# UVB_LED_Controller_-_current_balancing.net
KiCad netlist of a schematic drawn in Altium Designer
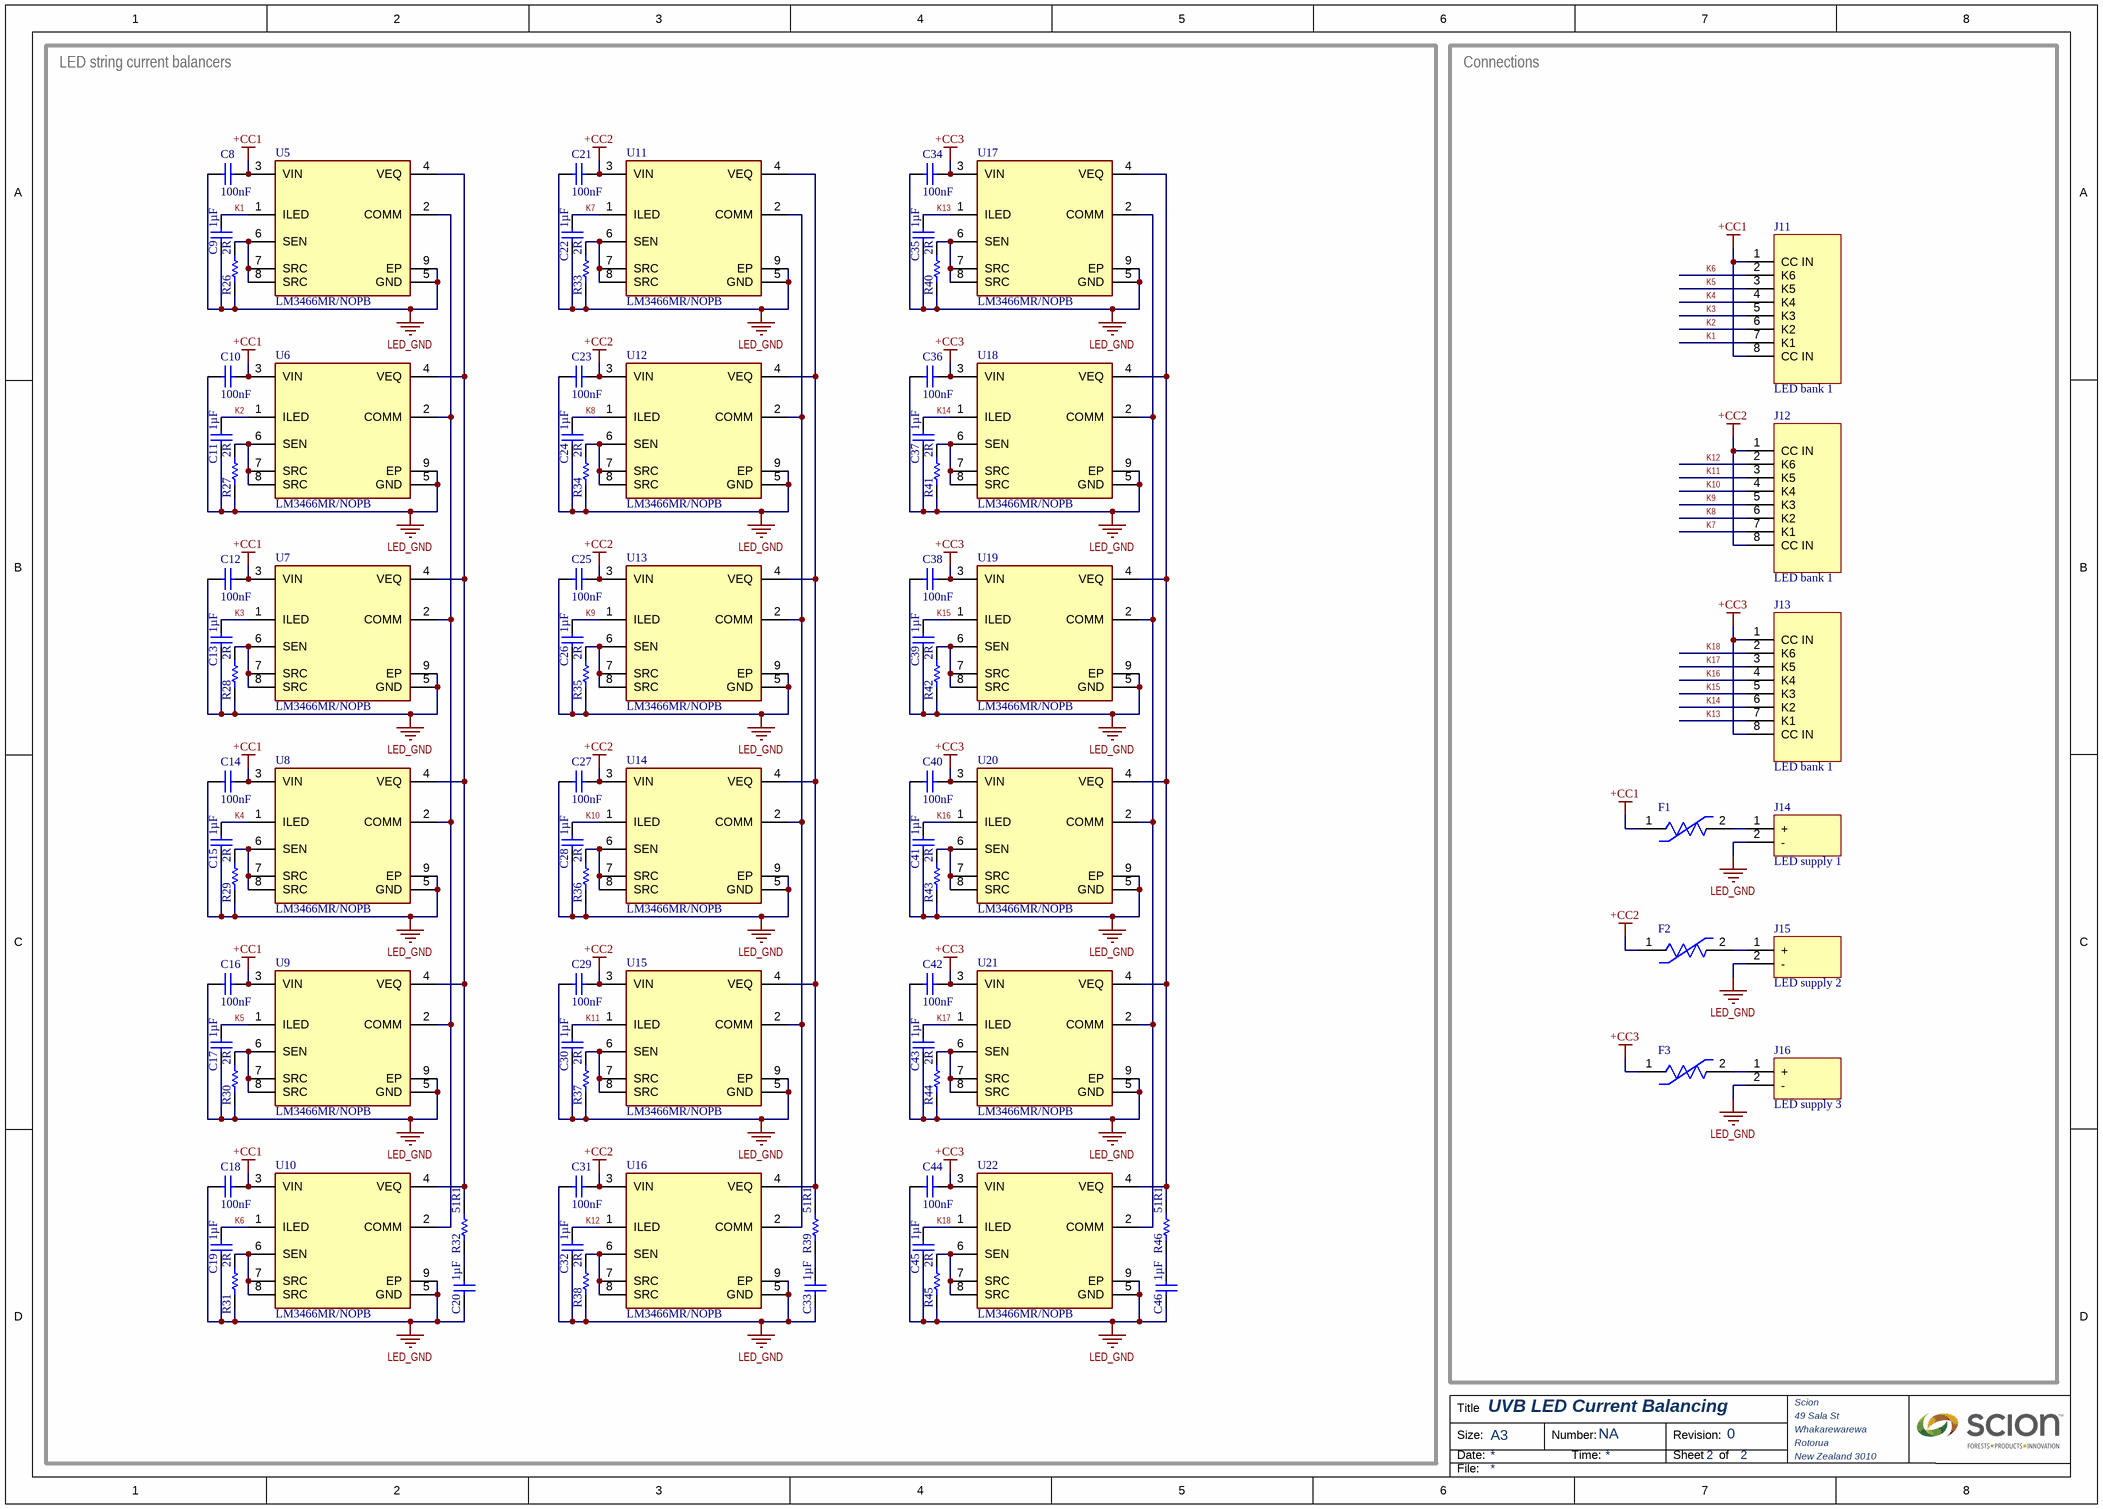
[diagram p0: UVB LED Controller - current balancing.SchDoc]

(export (version "E")
  (design (tool "Eeschema 10.0.6"))
  (components
    (comp (ref "C8")
      (value "100nF")
      (footprint "0603_CAP")
      (description "SMD Capacitor")
      (fields (field (name "Comment") "Capacitor"))
      (libsource (lib "Scion Research") (part "CMP-019-00005-2"))
    )
    (comp (ref "C9")
      (value "1µF")
      (footprint "0603_CAP")
      (description "SMD Capacitor")
      (fields (field (name "Comment") "Capacitor"))
      (libsource (lib "Scion Research") (part "CMP-019-00005-2"))
    )
    (comp (ref "C10")
      (value "100nF")
      (footprint "0603_CAP")
      (description "SMD Capacitor")
      (fields (field (name "Comment") "Capacitor"))
      (libsource (lib "Scion Research") (part "CMP-019-00005-2"))
    )
    (comp (ref "C11")
      (value "1µF")
      (footprint "0603_CAP")
      (description "SMD Capacitor")
      (fields (field (name "Comment") "Capacitor"))
      (libsource (lib "Scion Research") (part "CMP-019-00005-2"))
    )
    (comp (ref "C12")
      (value "100nF")
      (footprint "0603_CAP")
      (description "SMD Capacitor")
      (fields (field (name "Comment") "Capacitor"))
      (libsource (lib "Scion Research") (part "CMP-019-00005-2"))
    )
    (comp (ref "C13")
      (value "1µF")
      (footprint "0603_CAP")
      (description "SMD Capacitor")
      (fields (field (name "Comment") "Capacitor"))
      (libsource (lib "Scion Research") (part "CMP-019-00005-2"))
    )
    (comp (ref "C14")
      (value "100nF")
      (footprint "0603_CAP")
      (description "SMD Capacitor")
      (fields (field (name "Comment") "Capacitor"))
      (libsource (lib "Scion Research") (part "CMP-019-00005-2"))
    )
    (comp (ref "C15")
      (value "1µF")
      (footprint "0603_CAP")
      (description "SMD Capacitor")
      (fields (field (name "Comment") "Capacitor"))
      (libsource (lib "Scion Research") (part "CMP-019-00005-2"))
    )
    (comp (ref "C16")
      (value "100nF")
      (footprint "0603_CAP")
      (description "SMD Capacitor")
      (fields (field (name "Comment") "Capacitor"))
      (libsource (lib "Scion Research") (part "CMP-019-00005-2"))
    )
    (comp (ref "C17")
      (value "1µF")
      (footprint "0603_CAP")
      (description "SMD Capacitor")
      (fields (field (name "Comment") "Capacitor"))
      (libsource (lib "Scion Research") (part "CMP-019-00005-2"))
    )
    (comp (ref "C18")
      (value "100nF")
      (footprint "0603_CAP")
      (description "SMD Capacitor")
      (fields (field (name "Comment") "Capacitor"))
      (libsource (lib "Scion Research") (part "CMP-019-00005-2"))
    )
    (comp (ref "C19")
      (value "1µF")
      (footprint "0603_CAP")
      (description "SMD Capacitor")
      (fields (field (name "Comment") "Capacitor"))
      (libsource (lib "Scion Research") (part "CMP-019-00005-2"))
    )
    (comp (ref "C20")
      (value "1µF")
      (footprint "0603_CAP")
      (description "SMD Capacitor")
      (fields (field (name "Comment") "Capacitor"))
      (libsource (lib "Scion Research") (part "CMP-019-00005-2"))
    )
    (comp (ref "C21")
      (value "100nF")
      (footprint "0603_CAP")
      (description "SMD Capacitor")
      (fields (field (name "Comment") "Capacitor"))
      (libsource (lib "Scion Research") (part "CMP-019-00005-2"))
    )
    (comp (ref "C22")
      (value "1µF")
      (footprint "0603_CAP")
      (description "SMD Capacitor")
      (fields (field (name "Comment") "Capacitor"))
      (libsource (lib "Scion Research") (part "CMP-019-00005-2"))
    )
    (comp (ref "C23")
      (value "100nF")
      (footprint "0603_CAP")
      (description "SMD Capacitor")
      (fields (field (name "Comment") "Capacitor"))
      (libsource (lib "Scion Research") (part "CMP-019-00005-2"))
    )
    (comp (ref "C24")
      (value "1µF")
      (footprint "0603_CAP")
      (description "SMD Capacitor")
      (fields (field (name "Comment") "Capacitor"))
      (libsource (lib "Scion Research") (part "CMP-019-00005-2"))
    )
    (comp (ref "C25")
      (value "100nF")
      (footprint "0603_CAP")
      (description "SMD Capacitor")
      (fields (field (name "Comment") "Capacitor"))
      (libsource (lib "Scion Research") (part "CMP-019-00005-2"))
    )
    (comp (ref "C26")
      (value "1µF")
      (footprint "0603_CAP")
      (description "SMD Capacitor")
      (fields (field (name "Comment") "Capacitor"))
      (libsource (lib "Scion Research") (part "CMP-019-00005-2"))
    )
    (comp (ref "C27")
      (value "100nF")
      (footprint "0603_CAP")
      (description "SMD Capacitor")
      (fields (field (name "Comment") "Capacitor"))
      (libsource (lib "Scion Research") (part "CMP-019-00005-2"))
    )
    (comp (ref "C28")
      (value "1µF")
      (footprint "0603_CAP")
      (description "SMD Capacitor")
      (fields (field (name "Comment") "Capacitor"))
      (libsource (lib "Scion Research") (part "CMP-019-00005-2"))
    )
    (comp (ref "C29")
      (value "100nF")
      (footprint "0603_CAP")
      (description "SMD Capacitor")
      (fields (field (name "Comment") "Capacitor"))
      (libsource (lib "Scion Research") (part "CMP-019-00005-2"))
    )
    (comp (ref "C30")
      (value "1µF")
      (footprint "0603_CAP")
      (description "SMD Capacitor")
      (fields (field (name "Comment") "Capacitor"))
      (libsource (lib "Scion Research") (part "CMP-019-00005-2"))
    )
    (comp (ref "C31")
      (value "100nF")
      (footprint "0603_CAP")
      (description "SMD Capacitor")
      (fields (field (name "Comment") "Capacitor"))
      (libsource (lib "Scion Research") (part "CMP-019-00005-2"))
    )
    (comp (ref "C32")
      (value "1µF")
      (footprint "0603_CAP")
      (description "SMD Capacitor")
      (fields (field (name "Comment") "Capacitor"))
      (libsource (lib "Scion Research") (part "CMP-019-00005-2"))
    )
    (comp (ref "C33")
      (value "1µF")
      (footprint "0603_CAP")
      (description "SMD Capacitor")
      (fields (field (name "Comment") "Capacitor"))
      (libsource (lib "Scion Research") (part "CMP-019-00005-2"))
    )
    (comp (ref "C34")
      (value "100nF")
      (footprint "0603_CAP")
      (description "SMD Capacitor")
      (fields (field (name "Comment") "Capacitor"))
      (libsource (lib "Scion Research") (part "CMP-019-00005-2"))
    )
    (comp (ref "C35")
      (value "1µF")
      (footprint "0603_CAP")
      (description "SMD Capacitor")
      (fields (field (name "Comment") "Capacitor"))
      (libsource (lib "Scion Research") (part "CMP-019-00005-2"))
    )
    (comp (ref "C36")
      (value "100nF")
      (footprint "0603_CAP")
      (description "SMD Capacitor")
      (fields (field (name "Comment") "Capacitor"))
      (libsource (lib "Scion Research") (part "CMP-019-00005-2"))
    )
    (comp (ref "C37")
      (value "1µF")
      (footprint "0603_CAP")
      (description "SMD Capacitor")
      (fields (field (name "Comment") "Capacitor"))
      (libsource (lib "Scion Research") (part "CMP-019-00005-2"))
    )
    (comp (ref "C38")
      (value "100nF")
      (footprint "0603_CAP")
      (description "SMD Capacitor")
      (fields (field (name "Comment") "Capacitor"))
      (libsource (lib "Scion Research") (part "CMP-019-00005-2"))
    )
    (comp (ref "C39")
      (value "1µF")
      (footprint "0603_CAP")
      (description "SMD Capacitor")
      (fields (field (name "Comment") "Capacitor"))
      (libsource (lib "Scion Research") (part "CMP-019-00005-2"))
    )
    (comp (ref "C40")
      (value "100nF")
      (footprint "0603_CAP")
      (description "SMD Capacitor")
      (fields (field (name "Comment") "Capacitor"))
      (libsource (lib "Scion Research") (part "CMP-019-00005-2"))
    )
    (comp (ref "C41")
      (value "1µF")
      (footprint "0603_CAP")
      (description "SMD Capacitor")
      (fields (field (name "Comment") "Capacitor"))
      (libsource (lib "Scion Research") (part "CMP-019-00005-2"))
    )
    (comp (ref "C42")
      (value "100nF")
      (footprint "0603_CAP")
      (description "SMD Capacitor")
      (fields (field (name "Comment") "Capacitor"))
      (libsource (lib "Scion Research") (part "CMP-019-00005-2"))
    )
    (comp (ref "C43")
      (value "1µF")
      (footprint "0603_CAP")
      (description "SMD Capacitor")
      (fields (field (name "Comment") "Capacitor"))
      (libsource (lib "Scion Research") (part "CMP-019-00005-2"))
    )
    (comp (ref "C44")
      (value "100nF")
      (footprint "0603_CAP")
      (description "SMD Capacitor")
      (fields (field (name "Comment") "Capacitor"))
      (libsource (lib "Scion Research") (part "CMP-019-00005-2"))
    )
    (comp (ref "C45")
      (value "1µF")
      (footprint "0603_CAP")
      (description "SMD Capacitor")
      (fields (field (name "Comment") "Capacitor"))
      (libsource (lib "Scion Research") (part "CMP-019-00005-2"))
    )
    (comp (ref "C46")
      (value "1µF")
      (footprint "0603_CAP")
      (description "SMD Capacitor")
      (fields (field (name "Comment") "Capacitor"))
      (libsource (lib "Scion Research") (part "CMP-019-00005-2"))
    )
    (comp (ref "F1")
      (value "0ZCF0100AF2A")
      (footprint "FP-0ZCF0100AF2A-MFG")
      (description "PTC Resettable Fuse 100A 0.5s 60VDC 0.09 Ohm 2-Pin 2920 T/R")
      (libsource (lib "Scion Research") (part "CMP-00051-1"))
    )
    (comp (ref "F2")
      (value "0ZCF0100AF2A")
      (footprint "FP-0ZCF0100AF2A-MFG")
      (description "PTC Resettable Fuse 100A 0.5s 60VDC 0.09 Ohm 2-Pin 2920 T/R")
      (libsource (lib "Scion Research") (part "CMP-00051-1"))
    )
    (comp (ref "F3")
      (value "0ZCF0100AF2A")
      (footprint "FP-0ZCF0100AF2A-MFG")
      (description "PTC Resettable Fuse 100A 0.5s 60VDC 0.09 Ohm 2-Pin 2920 T/R")
      (libsource (lib "Scion Research") (part "CMP-00051-1"))
    )
    (comp (ref "J11")
      (value "LED bank 1")
      (footprint "8P RA MOLEX Clik-MATE 1.5mm")
      (description "8 Pin Connector")
      (libsource (lib "Scion Research") (part "CMP-002-00084-5"))
    )
    (comp (ref "J12")
      (value "LED bank 1")
      (footprint "8P RA MOLEX Clik-MATE 1.5mm")
      (description "8 Pin Connector")
      (libsource (lib "Scion Research") (part "CMP-002-00084-5"))
    )
    (comp (ref "J13")
      (value "LED bank 1")
      (footprint "8P RA MOLEX Clik-MATE 1.5mm")
      (description "8 Pin Connector")
      (libsource (lib "Scion Research") (part "CMP-002-00084-5"))
    )
    (comp (ref "J14")
      (value "LED supply 1")
      (footprint "2P 3.81mm Header Plugable")
      (description "2 Pin Connector")
      (libsource (lib "Scion Research") (part "CMP-002-00074-8"))
    )
    (comp (ref "J15")
      (value "LED supply 2")
      (footprint "2P 3.81mm Header Plugable")
      (description "2 Pin Connector")
      (libsource (lib "Scion Research") (part "CMP-002-00074-8"))
    )
    (comp (ref "J16")
      (value "LED supply 3")
      (footprint "2P 3.81mm Header Plugable")
      (description "2 Pin Connector")
      (libsource (lib "Scion Research") (part "CMP-002-00074-8"))
    )
    (comp (ref "R26")
      (value "2R")
      (footprint "0603_RES")
      (description "SMD Resistor")
      (fields (field (name "Comment") "Resistor"))
      (libsource (lib "Scion Research") (part "Resistor SMD"))
    )
    (comp (ref "R27")
      (value "2R")
      (footprint "0603_RES")
      (description "SMD Resistor")
      (fields (field (name "Comment") "Resistor"))
      (libsource (lib "Scion Research") (part "Resistor SMD"))
    )
    (comp (ref "R28")
      (value "2R")
      (footprint "0603_RES")
      (description "SMD Resistor")
      (fields (field (name "Comment") "Resistor"))
      (libsource (lib "Scion Research") (part "Resistor SMD"))
    )
    (comp (ref "R29")
      (value "2R")
      (footprint "0603_RES")
      (description "SMD Resistor")
      (fields (field (name "Comment") "Resistor"))
      (libsource (lib "Scion Research") (part "Resistor SMD"))
    )
    (comp (ref "R30")
      (value "2R")
      (footprint "0603_RES")
      (description "SMD Resistor")
      (fields (field (name "Comment") "Resistor"))
      (libsource (lib "Scion Research") (part "Resistor SMD"))
    )
    (comp (ref "R31")
      (value "2R")
      (footprint "0603_RES")
      (description "SMD Resistor")
      (fields (field (name "Comment") "Resistor"))
      (libsource (lib "Scion Research") (part "Resistor SMD"))
    )
    (comp (ref "R32")
      (value "51R1")
      (footprint "0603_RES")
      (description "SMD Resistor")
      (fields (field (name "Comment") "Resistor"))
      (libsource (lib "Scion Research") (part "Resistor SMD"))
    )
    (comp (ref "R33")
      (value "2R")
      (footprint "0603_RES")
      (description "SMD Resistor")
      (fields (field (name "Comment") "Resistor"))
      (libsource (lib "Scion Research") (part "Resistor SMD"))
    )
    (comp (ref "R34")
      (value "2R")
      (footprint "0603_RES")
      (description "SMD Resistor")
      (fields (field (name "Comment") "Resistor"))
      (libsource (lib "Scion Research") (part "Resistor SMD"))
    )
    (comp (ref "R35")
      (value "2R")
      (footprint "0603_RES")
      (description "SMD Resistor")
      (fields (field (name "Comment") "Resistor"))
      (libsource (lib "Scion Research") (part "Resistor SMD"))
    )
    (comp (ref "R36")
      (value "2R")
      (footprint "0603_RES")
      (description "SMD Resistor")
      (fields (field (name "Comment") "Resistor"))
      (libsource (lib "Scion Research") (part "Resistor SMD"))
    )
    (comp (ref "R37")
      (value "2R")
      (footprint "0603_RES")
      (description "SMD Resistor")
      (fields (field (name "Comment") "Resistor"))
      (libsource (lib "Scion Research") (part "Resistor SMD"))
    )
    (comp (ref "R38")
      (value "2R")
      (footprint "0603_RES")
      (description "SMD Resistor")
      (fields (field (name "Comment") "Resistor"))
      (libsource (lib "Scion Research") (part "Resistor SMD"))
    )
    (comp (ref "R39")
      (value "51R1")
      (footprint "0603_RES")
      (description "SMD Resistor")
      (fields (field (name "Comment") "Resistor"))
      (libsource (lib "Scion Research") (part "Resistor SMD"))
    )
    (comp (ref "R40")
      (value "2R")
      (footprint "0603_RES")
      (description "SMD Resistor")
      (fields (field (name "Comment") "Resistor"))
      (libsource (lib "Scion Research") (part "Resistor SMD"))
    )
    (comp (ref "R41")
      (value "2R")
      (footprint "0603_RES")
      (description "SMD Resistor")
      (fields (field (name "Comment") "Resistor"))
      (libsource (lib "Scion Research") (part "Resistor SMD"))
    )
    (comp (ref "R42")
      (value "2R")
      (footprint "0603_RES")
      (description "SMD Resistor")
      (fields (field (name "Comment") "Resistor"))
      (libsource (lib "Scion Research") (part "Resistor SMD"))
    )
    (comp (ref "R43")
      (value "2R")
      (footprint "0603_RES")
      (description "SMD Resistor")
      (fields (field (name "Comment") "Resistor"))
      (libsource (lib "Scion Research") (part "Resistor SMD"))
    )
    (comp (ref "R44")
      (value "2R")
      (footprint "0603_RES")
      (description "SMD Resistor")
      (fields (field (name "Comment") "Resistor"))
      (libsource (lib "Scion Research") (part "Resistor SMD"))
    )
    (comp (ref "R45")
      (value "2R")
      (footprint "0603_RES")
      (description "SMD Resistor")
      (fields (field (name "Comment") "Resistor"))
      (libsource (lib "Scion Research") (part "Resistor SMD"))
    )
    (comp (ref "R46")
      (value "51R1")
      (footprint "0603_RES")
      (description "SMD Resistor")
      (fields (field (name "Comment") "Resistor"))
      (libsource (lib "Scion Research") (part "Resistor SMD"))
    )
    (comp (ref "U5")
      (value "LM3466MR/NOPB")
      (footprint "FP-DDA0008A-MFG")
      (description "IC LED DRIVER LIN 1.5A 8SOPWRPAD")
      (fields
        (field (name "OCTOPART") "https://octopart.com/lm3466mr%2Fnopb-texas+instruments-24813886")
        (field (name "MANUFACTURER") "Texas Instruments")
      )
      (libsource (lib "Altium Content Vault") (part "bbf2d4a7672cdca9c85cb40f8eabf8f"))
    )
    (comp (ref "U6")
      (value "LM3466MR/NOPB")
      (footprint "FP-DDA0008A-MFG")
      (description "IC LED DRIVER LIN 1.5A 8SOPWRPAD")
      (fields
        (field (name "OCTOPART") "https://octopart.com/lm3466mr%2Fnopb-texas+instruments-24813886")
        (field (name "MANUFACTURER") "Texas Instruments")
      )
      (libsource (lib "Altium Content Vault") (part "bbf2d4a7672cdca9c85cb40f8eabf8f"))
    )
    (comp (ref "U7")
      (value "LM3466MR/NOPB")
      (footprint "FP-DDA0008A-MFG")
      (description "IC LED DRIVER LIN 1.5A 8SOPWRPAD")
      (fields
        (field (name "OCTOPART") "https://octopart.com/lm3466mr%2Fnopb-texas+instruments-24813886")
        (field (name "MANUFACTURER") "Texas Instruments")
      )
      (libsource (lib "Altium Content Vault") (part "bbf2d4a7672cdca9c85cb40f8eabf8f"))
    )
    (comp (ref "U8")
      (value "LM3466MR/NOPB")
      (footprint "FP-DDA0008A-MFG")
      (description "IC LED DRIVER LIN 1.5A 8SOPWRPAD")
      (fields
        (field (name "OCTOPART") "https://octopart.com/lm3466mr%2Fnopb-texas+instruments-24813886")
        (field (name "MANUFACTURER") "Texas Instruments")
      )
      (libsource (lib "Altium Content Vault") (part "bbf2d4a7672cdca9c85cb40f8eabf8f"))
    )
    (comp (ref "U9")
      (value "LM3466MR/NOPB")
      (footprint "FP-DDA0008A-MFG")
      (description "IC LED DRIVER LIN 1.5A 8SOPWRPAD")
      (fields
        (field (name "OCTOPART") "https://octopart.com/lm3466mr%2Fnopb-texas+instruments-24813886")
        (field (name "MANUFACTURER") "Texas Instruments")
      )
      (libsource (lib "Altium Content Vault") (part "bbf2d4a7672cdca9c85cb40f8eabf8f"))
    )
    (comp (ref "U10")
      (value "LM3466MR/NOPB")
      (footprint "FP-DDA0008A-MFG")
      (description "IC LED DRIVER LIN 1.5A 8SOPWRPAD")
      (fields
        (field (name "OCTOPART") "https://octopart.com/lm3466mr%2Fnopb-texas+instruments-24813886")
        (field (name "MANUFACTURER") "Texas Instruments")
      )
      (libsource (lib "Altium Content Vault") (part "bbf2d4a7672cdca9c85cb40f8eabf8f"))
    )
    (comp (ref "U11")
      (value "LM3466MR/NOPB")
      (footprint "FP-DDA0008A-MFG")
      (description "IC LED DRIVER LIN 1.5A 8SOPWRPAD")
      (fields
        (field (name "OCTOPART") "https://octopart.com/lm3466mr%2Fnopb-texas+instruments-24813886")
        (field (name "MANUFACTURER") "Texas Instruments")
      )
      (libsource (lib "Altium Content Vault") (part "bbf2d4a7672cdca9c85cb40f8eabf8f"))
    )
    (comp (ref "U12")
      (value "LM3466MR/NOPB")
      (footprint "FP-DDA0008A-MFG")
      (description "IC LED DRIVER LIN 1.5A 8SOPWRPAD")
      (fields
        (field (name "OCTOPART") "https://octopart.com/lm3466mr%2Fnopb-texas+instruments-24813886")
        (field (name "MANUFACTURER") "Texas Instruments")
      )
      (libsource (lib "Altium Content Vault") (part "bbf2d4a7672cdca9c85cb40f8eabf8f"))
    )
    (comp (ref "U13")
      (value "LM3466MR/NOPB")
      (footprint "FP-DDA0008A-MFG")
      (description "IC LED DRIVER LIN 1.5A 8SOPWRPAD")
      (fields
        (field (name "OCTOPART") "https://octopart.com/lm3466mr%2Fnopb-texas+instruments-24813886")
        (field (name "MANUFACTURER") "Texas Instruments")
      )
      (libsource (lib "Altium Content Vault") (part "bbf2d4a7672cdca9c85cb40f8eabf8f"))
    )
    (comp (ref "U14")
      (value "LM3466MR/NOPB")
      (footprint "FP-DDA0008A-MFG")
      (description "IC LED DRIVER LIN 1.5A 8SOPWRPAD")
      (fields
        (field (name "OCTOPART") "https://octopart.com/lm3466mr%2Fnopb-texas+instruments-24813886")
        (field (name "MANUFACTURER") "Texas Instruments")
      )
      (libsource (lib "Altium Content Vault") (part "bbf2d4a7672cdca9c85cb40f8eabf8f"))
    )
    (comp (ref "U15")
      (value "LM3466MR/NOPB")
      (footprint "FP-DDA0008A-MFG")
      (description "IC LED DRIVER LIN 1.5A 8SOPWRPAD")
      (fields
        (field (name "OCTOPART") "https://octopart.com/lm3466mr%2Fnopb-texas+instruments-24813886")
        (field (name "MANUFACTURER") "Texas Instruments")
      )
      (libsource (lib "Altium Content Vault") (part "bbf2d4a7672cdca9c85cb40f8eabf8f"))
    )
    (comp (ref "U16")
      (value "LM3466MR/NOPB")
      (footprint "FP-DDA0008A-MFG")
      (description "IC LED DRIVER LIN 1.5A 8SOPWRPAD")
      (fields
        (field (name "OCTOPART") "https://octopart.com/lm3466mr%2Fnopb-texas+instruments-24813886")
        (field (name "MANUFACTURER") "Texas Instruments")
      )
      (libsource (lib "Altium Content Vault") (part "bbf2d4a7672cdca9c85cb40f8eabf8f"))
    )
    (comp (ref "U17")
      (value "LM3466MR/NOPB")
      (footprint "FP-DDA0008A-MFG")
      (description "IC LED DRIVER LIN 1.5A 8SOPWRPAD")
      (fields
        (field (name "OCTOPART") "https://octopart.com/lm3466mr%2Fnopb-texas+instruments-24813886")
        (field (name "MANUFACTURER") "Texas Instruments")
      )
      (libsource (lib "Altium Content Vault") (part "bbf2d4a7672cdca9c85cb40f8eabf8f"))
    )
    (comp (ref "U18")
      (value "LM3466MR/NOPB")
      (footprint "FP-DDA0008A-MFG")
      (description "IC LED DRIVER LIN 1.5A 8SOPWRPAD")
      (fields
        (field (name "OCTOPART") "https://octopart.com/lm3466mr%2Fnopb-texas+instruments-24813886")
        (field (name "MANUFACTURER") "Texas Instruments")
      )
      (libsource (lib "Altium Content Vault") (part "bbf2d4a7672cdca9c85cb40f8eabf8f"))
    )
    (comp (ref "U19")
      (value "LM3466MR/NOPB")
      (footprint "FP-DDA0008A-MFG")
      (description "IC LED DRIVER LIN 1.5A 8SOPWRPAD")
      (fields
        (field (name "OCTOPART") "https://octopart.com/lm3466mr%2Fnopb-texas+instruments-24813886")
        (field (name "MANUFACTURER") "Texas Instruments")
      )
      (libsource (lib "Altium Content Vault") (part "bbf2d4a7672cdca9c85cb40f8eabf8f"))
    )
    (comp (ref "U20")
      (value "LM3466MR/NOPB")
      (footprint "FP-DDA0008A-MFG")
      (description "IC LED DRIVER LIN 1.5A 8SOPWRPAD")
      (fields
        (field (name "OCTOPART") "https://octopart.com/lm3466mr%2Fnopb-texas+instruments-24813886")
        (field (name "MANUFACTURER") "Texas Instruments")
      )
      (libsource (lib "Altium Content Vault") (part "bbf2d4a7672cdca9c85cb40f8eabf8f"))
    )
    (comp (ref "U21")
      (value "LM3466MR/NOPB")
      (footprint "FP-DDA0008A-MFG")
      (description "IC LED DRIVER LIN 1.5A 8SOPWRPAD")
      (fields
        (field (name "OCTOPART") "https://octopart.com/lm3466mr%2Fnopb-texas+instruments-24813886")
        (field (name "MANUFACTURER") "Texas Instruments")
      )
      (libsource (lib "Altium Content Vault") (part "bbf2d4a7672cdca9c85cb40f8eabf8f"))
    )
    (comp (ref "U22")
      (value "LM3466MR/NOPB")
      (footprint "FP-DDA0008A-MFG")
      (description "IC LED DRIVER LIN 1.5A 8SOPWRPAD")
      (fields
        (field (name "OCTOPART") "https://octopart.com/lm3466mr%2Fnopb-texas+instruments-24813886")
        (field (name "MANUFACTURER") "Texas Instruments")
      )
      (libsource (lib "Altium Content Vault") (part "bbf2d4a7672cdca9c85cb40f8eabf8f"))
    )
  )
  (nets
    (net (code "1") (name "+CC1") (class "Default")
      (node (ref "C10") (pin "1") (pinfunction "1_1") (pintype "passive"))
      (node (ref "C12") (pin "1") (pinfunction "1_1") (pintype "passive"))
      (node (ref "C14") (pin "1") (pinfunction "1_1") (pintype "passive"))
      (node (ref "C16") (pin "1") (pinfunction "1_1") (pintype "passive"))
      (node (ref "C18") (pin "1") (pinfunction "1_1") (pintype "passive"))
      (node (ref "C8") (pin "1") (pinfunction "1_1") (pintype "passive"))
      (node (ref "F1") (pin "1") (pinfunction "1_1") (pintype "passive"))
      (node (ref "J11") (pin "1") (pinfunction "CC_IN_1") (pintype "passive"))
      (node (ref "J11") (pin "8") (pinfunction "CC_IN_8") (pintype "passive"))
      (node (ref "U10") (pin "3") (pinfunction "VIN_3") (pintype "power_in"))
      (node (ref "U5") (pin "3") (pinfunction "VIN_3") (pintype "power_in"))
      (node (ref "U6") (pin "3") (pinfunction "VIN_3") (pintype "power_in"))
      (node (ref "U7") (pin "3") (pinfunction "VIN_3") (pintype "power_in"))
      (node (ref "U8") (pin "3") (pinfunction "VIN_3") (pintype "power_in"))
      (node (ref "U9") (pin "3") (pinfunction "VIN_3") (pintype "power_in"))
    )
    (net (code "2") (name "+CC2") (class "Default")
      (node (ref "C21") (pin "1") (pinfunction "1_1") (pintype "passive"))
      (node (ref "C23") (pin "1") (pinfunction "1_1") (pintype "passive"))
      (node (ref "C25") (pin "1") (pinfunction "1_1") (pintype "passive"))
      (node (ref "C27") (pin "1") (pinfunction "1_1") (pintype "passive"))
      (node (ref "C29") (pin "1") (pinfunction "1_1") (pintype "passive"))
      (node (ref "C31") (pin "1") (pinfunction "1_1") (pintype "passive"))
      (node (ref "F2") (pin "1") (pinfunction "1_1") (pintype "passive"))
      (node (ref "J12") (pin "1") (pinfunction "CC_IN_1") (pintype "passive"))
      (node (ref "J12") (pin "8") (pinfunction "CC_IN_8") (pintype "passive"))
      (node (ref "U11") (pin "3") (pinfunction "VIN_3") (pintype "power_in"))
      (node (ref "U12") (pin "3") (pinfunction "VIN_3") (pintype "power_in"))
      (node (ref "U13") (pin "3") (pinfunction "VIN_3") (pintype "power_in"))
      (node (ref "U14") (pin "3") (pinfunction "VIN_3") (pintype "power_in"))
      (node (ref "U15") (pin "3") (pinfunction "VIN_3") (pintype "power_in"))
      (node (ref "U16") (pin "3") (pinfunction "VIN_3") (pintype "power_in"))
    )
    (net (code "3") (name "+CC3") (class "Default")
      (node (ref "C34") (pin "1") (pinfunction "1_1") (pintype "passive"))
      (node (ref "C36") (pin "1") (pinfunction "1_1") (pintype "passive"))
      (node (ref "C38") (pin "1") (pinfunction "1_1") (pintype "passive"))
      (node (ref "C40") (pin "1") (pinfunction "1_1") (pintype "passive"))
      (node (ref "C42") (pin "1") (pinfunction "1_1") (pintype "passive"))
      (node (ref "C44") (pin "1") (pinfunction "1_1") (pintype "passive"))
      (node (ref "F3") (pin "1") (pinfunction "1_1") (pintype "passive"))
      (node (ref "J13") (pin "1") (pinfunction "CC_IN_1") (pintype "passive"))
      (node (ref "J13") (pin "8") (pinfunction "CC_IN_8") (pintype "passive"))
      (node (ref "U17") (pin "3") (pinfunction "VIN_3") (pintype "power_in"))
      (node (ref "U18") (pin "3") (pinfunction "VIN_3") (pintype "power_in"))
      (node (ref "U19") (pin "3") (pinfunction "VIN_3") (pintype "power_in"))
      (node (ref "U20") (pin "3") (pinfunction "VIN_3") (pintype "power_in"))
      (node (ref "U21") (pin "3") (pinfunction "VIN_3") (pintype "power_in"))
      (node (ref "U22") (pin "3") (pinfunction "VIN_3") (pintype "power_in"))
    )
    (net (code "4") (name "/K1") (class "Default")
      (node (ref "C9") (pin "1") (pinfunction "1_1") (pintype "passive"))
      (node (ref "J11") (pin "7") (pinfunction "K1_7") (pintype "passive"))
      (node (ref "U5") (pin "1") (pinfunction "ILED_1") (pintype "passive"))
    )
    (net (code "5") (name "/K2") (class "Default")
      (node (ref "C11") (pin "1") (pinfunction "1_1") (pintype "passive"))
      (node (ref "J11") (pin "6") (pinfunction "K2_6") (pintype "passive"))
      (node (ref "U6") (pin "1") (pinfunction "ILED_1") (pintype "passive"))
    )
    (net (code "6") (name "/K3") (class "Default")
      (node (ref "C13") (pin "1") (pinfunction "1_1") (pintype "passive"))
      (node (ref "J11") (pin "5") (pinfunction "K3_5") (pintype "passive"))
      (node (ref "U7") (pin "1") (pinfunction "ILED_1") (pintype "passive"))
    )
    (net (code "7") (name "/K4") (class "Default")
      (node (ref "C15") (pin "1") (pinfunction "1_1") (pintype "passive"))
      (node (ref "J11") (pin "4") (pinfunction "K4_4") (pintype "passive"))
      (node (ref "U8") (pin "1") (pinfunction "ILED_1") (pintype "passive"))
    )
    (net (code "8") (name "/K5") (class "Default")
      (node (ref "C17") (pin "1") (pinfunction "1_1") (pintype "passive"))
      (node (ref "J11") (pin "3") (pinfunction "K5_3") (pintype "passive"))
      (node (ref "U9") (pin "1") (pinfunction "ILED_1") (pintype "passive"))
    )
    (net (code "9") (name "/K6") (class "Default")
      (node (ref "C19") (pin "1") (pinfunction "1_1") (pintype "passive"))
      (node (ref "J11") (pin "2") (pinfunction "K6_2") (pintype "passive"))
      (node (ref "U10") (pin "1") (pinfunction "ILED_1") (pintype "passive"))
    )
    (net (code "10") (name "/K7") (class "Default")
      (node (ref "C22") (pin "1") (pinfunction "1_1") (pintype "passive"))
      (node (ref "J12") (pin "7") (pinfunction "K1_7") (pintype "passive"))
      (node (ref "U11") (pin "1") (pinfunction "ILED_1") (pintype "passive"))
    )
    (net (code "11") (name "/K8") (class "Default")
      (node (ref "C24") (pin "1") (pinfunction "1_1") (pintype "passive"))
      (node (ref "J12") (pin "6") (pinfunction "K2_6") (pintype "passive"))
      (node (ref "U12") (pin "1") (pinfunction "ILED_1") (pintype "passive"))
    )
    (net (code "12") (name "/K9") (class "Default")
      (node (ref "C26") (pin "1") (pinfunction "1_1") (pintype "passive"))
      (node (ref "J12") (pin "5") (pinfunction "K3_5") (pintype "passive"))
      (node (ref "U13") (pin "1") (pinfunction "ILED_1") (pintype "passive"))
    )
    (net (code "13") (name "/K10") (class "Default")
      (node (ref "C28") (pin "1") (pinfunction "1_1") (pintype "passive"))
      (node (ref "J12") (pin "4") (pinfunction "K4_4") (pintype "passive"))
      (node (ref "U14") (pin "1") (pinfunction "ILED_1") (pintype "passive"))
    )
    (net (code "14") (name "/K11") (class "Default")
      (node (ref "C30") (pin "1") (pinfunction "1_1") (pintype "passive"))
      (node (ref "J12") (pin "3") (pinfunction "K5_3") (pintype "passive"))
      (node (ref "U15") (pin "1") (pinfunction "ILED_1") (pintype "passive"))
    )
    (net (code "15") (name "/K12") (class "Default")
      (node (ref "C32") (pin "1") (pinfunction "1_1") (pintype "passive"))
      (node (ref "J12") (pin "2") (pinfunction "K6_2") (pintype "passive"))
      (node (ref "U16") (pin "1") (pinfunction "ILED_1") (pintype "passive"))
    )
    (net (code "16") (name "/K13") (class "Default")
      (node (ref "C35") (pin "1") (pinfunction "1_1") (pintype "passive"))
      (node (ref "J13") (pin "7") (pinfunction "K1_7") (pintype "passive"))
      (node (ref "U17") (pin "1") (pinfunction "ILED_1") (pintype "passive"))
    )
    (net (code "17") (name "/K14") (class "Default")
      (node (ref "C37") (pin "1") (pinfunction "1_1") (pintype "passive"))
      (node (ref "J13") (pin "6") (pinfunction "K2_6") (pintype "passive"))
      (node (ref "U18") (pin "1") (pinfunction "ILED_1") (pintype "passive"))
    )
    (net (code "18") (name "/K15") (class "Default")
      (node (ref "C39") (pin "1") (pinfunction "1_1") (pintype "passive"))
      (node (ref "J13") (pin "5") (pinfunction "K3_5") (pintype "passive"))
      (node (ref "U19") (pin "1") (pinfunction "ILED_1") (pintype "passive"))
    )
    (net (code "19") (name "/K16") (class "Default")
      (node (ref "C41") (pin "1") (pinfunction "1_1") (pintype "passive"))
      (node (ref "J13") (pin "4") (pinfunction "K4_4") (pintype "passive"))
      (node (ref "U20") (pin "1") (pinfunction "ILED_1") (pintype "passive"))
    )
    (net (code "20") (name "/K17") (class "Default")
      (node (ref "C43") (pin "1") (pinfunction "1_1") (pintype "passive"))
      (node (ref "J13") (pin "3") (pinfunction "K5_3") (pintype "passive"))
      (node (ref "U21") (pin "1") (pinfunction "ILED_1") (pintype "passive"))
    )
    (net (code "21") (name "/K18") (class "Default")
      (node (ref "C45") (pin "1") (pinfunction "1_1") (pintype "passive"))
      (node (ref "J13") (pin "2") (pinfunction "K6_2") (pintype "passive"))
      (node (ref "U22") (pin "1") (pinfunction "ILED_1") (pintype "passive"))
    )
    (net (code "22") (name "LED_GND") (class "Default")
      (node (ref "C10") (pin "2") (pinfunction "2_2") (pintype "passive"))
      (node (ref "C11") (pin "2") (pinfunction "2_2") (pintype "passive"))
      (node (ref "C12") (pin "2") (pinfunction "2_2") (pintype "passive"))
      (node (ref "C13") (pin "2") (pinfunction "2_2") (pintype "passive"))
      (node (ref "C14") (pin "2") (pinfunction "2_2") (pintype "passive"))
      (node (ref "C15") (pin "2") (pinfunction "2_2") (pintype "passive"))
      (node (ref "C16") (pin "2") (pinfunction "2_2") (pintype "passive"))
      (node (ref "C17") (pin "2") (pinfunction "2_2") (pintype "passive"))
      (node (ref "C18") (pin "2") (pinfunction "2_2") (pintype "passive"))
      (node (ref "C19") (pin "2") (pinfunction "2_2") (pintype "passive"))
      (node (ref "C20") (pin "1") (pinfunction "1_1") (pintype "passive"))
      (node (ref "C21") (pin "2") (pinfunction "2_2") (pintype "passive"))
      (node (ref "C22") (pin "2") (pinfunction "2_2") (pintype "passive"))
      (node (ref "C23") (pin "2") (pinfunction "2_2") (pintype "passive"))
      (node (ref "C24") (pin "2") (pinfunction "2_2") (pintype "passive"))
      (node (ref "C25") (pin "2") (pinfunction "2_2") (pintype "passive"))
      (node (ref "C26") (pin "2") (pinfunction "2_2") (pintype "passive"))
      (node (ref "C27") (pin "2") (pinfunction "2_2") (pintype "passive"))
      (node (ref "C28") (pin "2") (pinfunction "2_2") (pintype "passive"))
      (node (ref "C29") (pin "2") (pinfunction "2_2") (pintype "passive"))
      (node (ref "C30") (pin "2") (pinfunction "2_2") (pintype "passive"))
      (node (ref "C31") (pin "2") (pinfunction "2_2") (pintype "passive"))
      (node (ref "C32") (pin "2") (pinfunction "2_2") (pintype "passive"))
      (node (ref "C33") (pin "1") (pinfunction "1_1") (pintype "passive"))
      (node (ref "C34") (pin "2") (pinfunction "2_2") (pintype "passive"))
      (node (ref "C35") (pin "2") (pinfunction "2_2") (pintype "passive"))
      (node (ref "C36") (pin "2") (pinfunction "2_2") (pintype "passive"))
      (node (ref "C37") (pin "2") (pinfunction "2_2") (pintype "passive"))
      (node (ref "C38") (pin "2") (pinfunction "2_2") (pintype "passive"))
      (node (ref "C39") (pin "2") (pinfunction "2_2") (pintype "passive"))
      (node (ref "C40") (pin "2") (pinfunction "2_2") (pintype "passive"))
      (node (ref "C41") (pin "2") (pinfunction "2_2") (pintype "passive"))
      (node (ref "C42") (pin "2") (pinfunction "2_2") (pintype "passive"))
      (node (ref "C43") (pin "2") (pinfunction "2_2") (pintype "passive"))
      (node (ref "C44") (pin "2") (pinfunction "2_2") (pintype "passive"))
      (node (ref "C45") (pin "2") (pinfunction "2_2") (pintype "passive"))
      (node (ref "C46") (pin "1") (pinfunction "1_1") (pintype "passive"))
      (node (ref "C8") (pin "2") (pinfunction "2_2") (pintype "passive"))
      (node (ref "C9") (pin "2") (pinfunction "2_2") (pintype "passive"))
      (node (ref "J14") (pin "2") (pinfunction "-_2") (pintype "passive"))
      (node (ref "J15") (pin "2") (pinfunction "-_2") (pintype "passive"))
      (node (ref "J16") (pin "2") (pinfunction "-_2") (pintype "passive"))
      (node (ref "R26") (pin "1") (pinfunction "1_1") (pintype "passive"))
      (node (ref "R27") (pin "1") (pinfunction "1_1") (pintype "passive"))
      (node (ref "R28") (pin "1") (pinfunction "1_1") (pintype "passive"))
      (node (ref "R29") (pin "1") (pinfunction "1_1") (pintype "passive"))
      (node (ref "R30") (pin "1") (pinfunction "1_1") (pintype "passive"))
      (node (ref "R31") (pin "1") (pinfunction "1_1") (pintype "passive"))
      (node (ref "R33") (pin "1") (pinfunction "1_1") (pintype "passive"))
      (node (ref "R34") (pin "1") (pinfunction "1_1") (pintype "passive"))
      (node (ref "R35") (pin "1") (pinfunction "1_1") (pintype "passive"))
      (node (ref "R36") (pin "1") (pinfunction "1_1") (pintype "passive"))
      (node (ref "R37") (pin "1") (pinfunction "1_1") (pintype "passive"))
      (node (ref "R38") (pin "1") (pinfunction "1_1") (pintype "passive"))
      (node (ref "R40") (pin "1") (pinfunction "1_1") (pintype "passive"))
      (node (ref "R41") (pin "1") (pinfunction "1_1") (pintype "passive"))
      (node (ref "R42") (pin "1") (pinfunction "1_1") (pintype "passive"))
      (node (ref "R43") (pin "1") (pinfunction "1_1") (pintype "passive"))
      (node (ref "R44") (pin "1") (pinfunction "1_1") (pintype "passive"))
      (node (ref "R45") (pin "1") (pinfunction "1_1") (pintype "passive"))
      (node (ref "U10") (pin "5") (pinfunction "GND_5") (pintype "power_in"))
      (node (ref "U10") (pin "9") (pinfunction "EP_9") (pintype "passive"))
      (node (ref "U11") (pin "5") (pinfunction "GND_5") (pintype "power_in"))
      (node (ref "U11") (pin "9") (pinfunction "EP_9") (pintype "passive"))
      (node (ref "U12") (pin "5") (pinfunction "GND_5") (pintype "power_in"))
      (node (ref "U12") (pin "9") (pinfunction "EP_9") (pintype "passive"))
      (node (ref "U13") (pin "5") (pinfunction "GND_5") (pintype "power_in"))
      (node (ref "U13") (pin "9") (pinfunction "EP_9") (pintype "passive"))
      (node (ref "U14") (pin "5") (pinfunction "GND_5") (pintype "power_in"))
      (node (ref "U14") (pin "9") (pinfunction "EP_9") (pintype "passive"))
      (node (ref "U15") (pin "5") (pinfunction "GND_5") (pintype "power_in"))
      (node (ref "U15") (pin "9") (pinfunction "EP_9") (pintype "passive"))
      (node (ref "U16") (pin "5") (pinfunction "GND_5") (pintype "power_in"))
      (node (ref "U16") (pin "9") (pinfunction "EP_9") (pintype "passive"))
      (node (ref "U17") (pin "5") (pinfunction "GND_5") (pintype "power_in"))
      (node (ref "U17") (pin "9") (pinfunction "EP_9") (pintype "passive"))
      (node (ref "U18") (pin "5") (pinfunction "GND_5") (pintype "power_in"))
      (node (ref "U18") (pin "9") (pinfunction "EP_9") (pintype "passive"))
      (node (ref "U19") (pin "5") (pinfunction "GND_5") (pintype "power_in"))
      (node (ref "U19") (pin "9") (pinfunction "EP_9") (pintype "passive"))
      (node (ref "U20") (pin "5") (pinfunction "GND_5") (pintype "power_in"))
      (node (ref "U20") (pin "9") (pinfunction "EP_9") (pintype "passive"))
      (node (ref "U21") (pin "5") (pinfunction "GND_5") (pintype "power_in"))
      (node (ref "U21") (pin "9") (pinfunction "EP_9") (pintype "passive"))
      (node (ref "U22") (pin "5") (pinfunction "GND_5") (pintype "power_in"))
      (node (ref "U22") (pin "9") (pinfunction "EP_9") (pintype "passive"))
      (node (ref "U5") (pin "5") (pinfunction "GND_5") (pintype "power_in"))
      (node (ref "U5") (pin "9") (pinfunction "EP_9") (pintype "passive"))
      (node (ref "U6") (pin "5") (pinfunction "GND_5") (pintype "power_in"))
      (node (ref "U6") (pin "9") (pinfunction "EP_9") (pintype "passive"))
      (node (ref "U7") (pin "5") (pinfunction "GND_5") (pintype "power_in"))
      (node (ref "U7") (pin "9") (pinfunction "EP_9") (pintype "passive"))
      (node (ref "U8") (pin "5") (pinfunction "GND_5") (pintype "power_in"))
      (node (ref "U8") (pin "9") (pinfunction "EP_9") (pintype "passive"))
      (node (ref "U9") (pin "5") (pinfunction "GND_5") (pintype "power_in"))
      (node (ref "U9") (pin "9") (pinfunction "EP_9") (pintype "passive"))
    )
    (net (code "23") (name "Net-(C20-Pad2)") (class "Default")
      (node (ref "C20") (pin "2") (pinfunction "2_2") (pintype "passive"))
      (node (ref "R32") (pin "1") (pinfunction "1_1") (pintype "passive"))
    )
    (net (code "24") (name "Net-(C33-Pad2)") (class "Default")
      (node (ref "C33") (pin "2") (pinfunction "2_2") (pintype "passive"))
      (node (ref "R39") (pin "1") (pinfunction "1_1") (pintype "passive"))
    )
    (net (code "25") (name "Net-(C46-Pad2)") (class "Default")
      (node (ref "C46") (pin "2") (pinfunction "2_2") (pintype "passive"))
      (node (ref "R46") (pin "1") (pinfunction "1_1") (pintype "passive"))
    )
    (net (code "26") (name "Net-(J14-+)") (class "Default")
      (node (ref "F1") (pin "2") (pinfunction "2_2") (pintype "passive"))
      (node (ref "J14") (pin "1") (pinfunction "+_1") (pintype "passive"))
    )
    (net (code "27") (name "Net-(J15-+)") (class "Default")
      (node (ref "F2") (pin "2") (pinfunction "2_2") (pintype "passive"))
      (node (ref "J15") (pin "1") (pinfunction "+_1") (pintype "passive"))
    )
    (net (code "28") (name "Net-(J16-+)") (class "Default")
      (node (ref "F3") (pin "2") (pinfunction "2_2") (pintype "passive"))
      (node (ref "J16") (pin "1") (pinfunction "+_1") (pintype "passive"))
    )
    (net (code "29") (name "Net-(U5-SEN)") (class "Default")
      (node (ref "R26") (pin "2") (pinfunction "2_2") (pintype "passive"))
      (node (ref "U5") (pin "6") (pinfunction "SEN_6") (pintype "passive"))
      (node (ref "U5") (pin "7") (pinfunction "SRC_7") (pintype "passive"))
      (node (ref "U5") (pin "8") (pinfunction "SRC_8") (pintype "passive"))
    )
    (net (code "30") (name "Net-(U6-SEN)") (class "Default")
      (node (ref "R27") (pin "2") (pinfunction "2_2") (pintype "passive"))
      (node (ref "U6") (pin "6") (pinfunction "SEN_6") (pintype "passive"))
      (node (ref "U6") (pin "7") (pinfunction "SRC_7") (pintype "passive"))
      (node (ref "U6") (pin "8") (pinfunction "SRC_8") (pintype "passive"))
    )
    (net (code "31") (name "Net-(U7-SEN)") (class "Default")
      (node (ref "R28") (pin "2") (pinfunction "2_2") (pintype "passive"))
      (node (ref "U7") (pin "6") (pinfunction "SEN_6") (pintype "passive"))
      (node (ref "U7") (pin "7") (pinfunction "SRC_7") (pintype "passive"))
      (node (ref "U7") (pin "8") (pinfunction "SRC_8") (pintype "passive"))
    )
    (net (code "32") (name "Net-(U8-SEN)") (class "Default")
      (node (ref "R29") (pin "2") (pinfunction "2_2") (pintype "passive"))
      (node (ref "U8") (pin "6") (pinfunction "SEN_6") (pintype "passive"))
      (node (ref "U8") (pin "7") (pinfunction "SRC_7") (pintype "passive"))
      (node (ref "U8") (pin "8") (pinfunction "SRC_8") (pintype "passive"))
    )
    (net (code "33") (name "Net-(U9-SEN)") (class "Default")
      (node (ref "R30") (pin "2") (pinfunction "2_2") (pintype "passive"))
      (node (ref "U9") (pin "6") (pinfunction "SEN_6") (pintype "passive"))
      (node (ref "U9") (pin "7") (pinfunction "SRC_7") (pintype "passive"))
      (node (ref "U9") (pin "8") (pinfunction "SRC_8") (pintype "passive"))
    )
    (net (code "34") (name "Net-(U10-COMM)") (class "Default")
      (node (ref "U10") (pin "2") (pinfunction "COMM_2") (pintype "open_collector"))
      (node (ref "U5") (pin "2") (pinfunction "COMM_2") (pintype "open_collector"))
      (node (ref "U6") (pin "2") (pinfunction "COMM_2") (pintype "open_collector"))
      (node (ref "U7") (pin "2") (pinfunction "COMM_2") (pintype "open_collector"))
      (node (ref "U8") (pin "2") (pinfunction "COMM_2") (pintype "open_collector"))
      (node (ref "U9") (pin "2") (pinfunction "COMM_2") (pintype "open_collector"))
    )
    (net (code "35") (name "Net-(U10-SEN)") (class "Default")
      (node (ref "R31") (pin "2") (pinfunction "2_2") (pintype "passive"))
      (node (ref "U10") (pin "6") (pinfunction "SEN_6") (pintype "passive"))
      (node (ref "U10") (pin "7") (pinfunction "SRC_7") (pintype "passive"))
      (node (ref "U10") (pin "8") (pinfunction "SRC_8") (pintype "passive"))
    )
    (net (code "36") (name "Net-(U10-VEQ)") (class "Default")
      (node (ref "R32") (pin "2") (pinfunction "2_2") (pintype "passive"))
      (node (ref "U10") (pin "4") (pinfunction "VEQ_4") (pintype "passive"))
      (node (ref "U5") (pin "4") (pinfunction "VEQ_4") (pintype "passive"))
      (node (ref "U6") (pin "4") (pinfunction "VEQ_4") (pintype "passive"))
      (node (ref "U7") (pin "4") (pinfunction "VEQ_4") (pintype "passive"))
      (node (ref "U8") (pin "4") (pinfunction "VEQ_4") (pintype "passive"))
      (node (ref "U9") (pin "4") (pinfunction "VEQ_4") (pintype "passive"))
    )
    (net (code "37") (name "Net-(U11-COMM)") (class "Default")
      (node (ref "U11") (pin "2") (pinfunction "COMM_2") (pintype "open_collector"))
      (node (ref "U12") (pin "2") (pinfunction "COMM_2") (pintype "open_collector"))
      (node (ref "U13") (pin "2") (pinfunction "COMM_2") (pintype "open_collector"))
      (node (ref "U14") (pin "2") (pinfunction "COMM_2") (pintype "open_collector"))
      (node (ref "U15") (pin "2") (pinfunction "COMM_2") (pintype "open_collector"))
      (node (ref "U16") (pin "2") (pinfunction "COMM_2") (pintype "open_collector"))
    )
    (net (code "38") (name "Net-(U11-SEN)") (class "Default")
      (node (ref "R33") (pin "2") (pinfunction "2_2") (pintype "passive"))
      (node (ref "U11") (pin "6") (pinfunction "SEN_6") (pintype "passive"))
      (node (ref "U11") (pin "7") (pinfunction "SRC_7") (pintype "passive"))
      (node (ref "U11") (pin "8") (pinfunction "SRC_8") (pintype "passive"))
    )
    (net (code "39") (name "Net-(U11-VEQ)") (class "Default")
      (node (ref "R39") (pin "2") (pinfunction "2_2") (pintype "passive"))
      (node (ref "U11") (pin "4") (pinfunction "VEQ_4") (pintype "passive"))
      (node (ref "U12") (pin "4") (pinfunction "VEQ_4") (pintype "passive"))
      (node (ref "U13") (pin "4") (pinfunction "VEQ_4") (pintype "passive"))
      (node (ref "U14") (pin "4") (pinfunction "VEQ_4") (pintype "passive"))
      (node (ref "U15") (pin "4") (pinfunction "VEQ_4") (pintype "passive"))
      (node (ref "U16") (pin "4") (pinfunction "VEQ_4") (pintype "passive"))
    )
    (net (code "40") (name "Net-(U12-SEN)") (class "Default")
      (node (ref "R34") (pin "2") (pinfunction "2_2") (pintype "passive"))
      (node (ref "U12") (pin "6") (pinfunction "SEN_6") (pintype "passive"))
      (node (ref "U12") (pin "7") (pinfunction "SRC_7") (pintype "passive"))
      (node (ref "U12") (pin "8") (pinfunction "SRC_8") (pintype "passive"))
    )
    (net (code "41") (name "Net-(U13-SEN)") (class "Default")
      (node (ref "R35") (pin "2") (pinfunction "2_2") (pintype "passive"))
      (node (ref "U13") (pin "6") (pinfunction "SEN_6") (pintype "passive"))
      (node (ref "U13") (pin "7") (pinfunction "SRC_7") (pintype "passive"))
      (node (ref "U13") (pin "8") (pinfunction "SRC_8") (pintype "passive"))
    )
    (net (code "42") (name "Net-(U14-SEN)") (class "Default")
      (node (ref "R36") (pin "2") (pinfunction "2_2") (pintype "passive"))
      (node (ref "U14") (pin "6") (pinfunction "SEN_6") (pintype "passive"))
      (node (ref "U14") (pin "7") (pinfunction "SRC_7") (pintype "passive"))
      (node (ref "U14") (pin "8") (pinfunction "SRC_8") (pintype "passive"))
    )
    (net (code "43") (name "Net-(U15-SEN)") (class "Default")
      (node (ref "R37") (pin "2") (pinfunction "2_2") (pintype "passive"))
      (node (ref "U15") (pin "6") (pinfunction "SEN_6") (pintype "passive"))
      (node (ref "U15") (pin "7") (pinfunction "SRC_7") (pintype "passive"))
      (node (ref "U15") (pin "8") (pinfunction "SRC_8") (pintype "passive"))
    )
    (net (code "44") (name "Net-(U16-SEN)") (class "Default")
      (node (ref "R38") (pin "2") (pinfunction "2_2") (pintype "passive"))
      (node (ref "U16") (pin "6") (pinfunction "SEN_6") (pintype "passive"))
      (node (ref "U16") (pin "7") (pinfunction "SRC_7") (pintype "passive"))
      (node (ref "U16") (pin "8") (pinfunction "SRC_8") (pintype "passive"))
    )
    (net (code "45") (name "Net-(U17-COMM)") (class "Default")
      (node (ref "U17") (pin "2") (pinfunction "COMM_2") (pintype "open_collector"))
      (node (ref "U18") (pin "2") (pinfunction "COMM_2") (pintype "open_collector"))
      (node (ref "U19") (pin "2") (pinfunction "COMM_2") (pintype "open_collector"))
      (node (ref "U20") (pin "2") (pinfunction "COMM_2") (pintype "open_collector"))
      (node (ref "U21") (pin "2") (pinfunction "COMM_2") (pintype "open_collector"))
      (node (ref "U22") (pin "2") (pinfunction "COMM_2") (pintype "open_collector"))
    )
    (net (code "46") (name "Net-(U17-SEN)") (class "Default")
      (node (ref "R40") (pin "2") (pinfunction "2_2") (pintype "passive"))
      (node (ref "U17") (pin "6") (pinfunction "SEN_6") (pintype "passive"))
      (node (ref "U17") (pin "7") (pinfunction "SRC_7") (pintype "passive"))
      (node (ref "U17") (pin "8") (pinfunction "SRC_8") (pintype "passive"))
    )
    (net (code "47") (name "Net-(U17-VEQ)") (class "Default")
      (node (ref "R46") (pin "2") (pinfunction "2_2") (pintype "passive"))
      (node (ref "U17") (pin "4") (pinfunction "VEQ_4") (pintype "passive"))
      (node (ref "U18") (pin "4") (pinfunction "VEQ_4") (pintype "passive"))
      (node (ref "U19") (pin "4") (pinfunction "VEQ_4") (pintype "passive"))
      (node (ref "U20") (pin "4") (pinfunction "VEQ_4") (pintype "passive"))
      (node (ref "U21") (pin "4") (pinfunction "VEQ_4") (pintype "passive"))
      (node (ref "U22") (pin "4") (pinfunction "VEQ_4") (pintype "passive"))
    )
    (net (code "48") (name "Net-(U18-SEN)") (class "Default")
      (node (ref "R41") (pin "2") (pinfunction "2_2") (pintype "passive"))
      (node (ref "U18") (pin "6") (pinfunction "SEN_6") (pintype "passive"))
      (node (ref "U18") (pin "7") (pinfunction "SRC_7") (pintype "passive"))
      (node (ref "U18") (pin "8") (pinfunction "SRC_8") (pintype "passive"))
    )
    (net (code "49") (name "Net-(U19-SEN)") (class "Default")
      (node (ref "R42") (pin "2") (pinfunction "2_2") (pintype "passive"))
      (node (ref "U19") (pin "6") (pinfunction "SEN_6") (pintype "passive"))
      (node (ref "U19") (pin "7") (pinfunction "SRC_7") (pintype "passive"))
      (node (ref "U19") (pin "8") (pinfunction "SRC_8") (pintype "passive"))
    )
    (net (code "50") (name "Net-(U20-SEN)") (class "Default")
      (node (ref "R43") (pin "2") (pinfunction "2_2") (pintype "passive"))
      (node (ref "U20") (pin "6") (pinfunction "SEN_6") (pintype "passive"))
      (node (ref "U20") (pin "7") (pinfunction "SRC_7") (pintype "passive"))
      (node (ref "U20") (pin "8") (pinfunction "SRC_8") (pintype "passive"))
    )
    (net (code "51") (name "Net-(U21-SEN)") (class "Default")
      (node (ref "R44") (pin "2") (pinfunction "2_2") (pintype "passive"))
      (node (ref "U21") (pin "6") (pinfunction "SEN_6") (pintype "passive"))
      (node (ref "U21") (pin "7") (pinfunction "SRC_7") (pintype "passive"))
      (node (ref "U21") (pin "8") (pinfunction "SRC_8") (pintype "passive"))
    )
    (net (code "52") (name "Net-(U22-SEN)") (class "Default")
      (node (ref "R45") (pin "2") (pinfunction "2_2") (pintype "passive"))
      (node (ref "U22") (pin "6") (pinfunction "SEN_6") (pintype "passive"))
      (node (ref "U22") (pin "7") (pinfunction "SRC_7") (pintype "passive"))
      (node (ref "U22") (pin "8") (pinfunction "SRC_8") (pintype "passive"))
    )
  )
)
